# Maple5.net
KiCad netlist of a schematic drawn in EAGLE
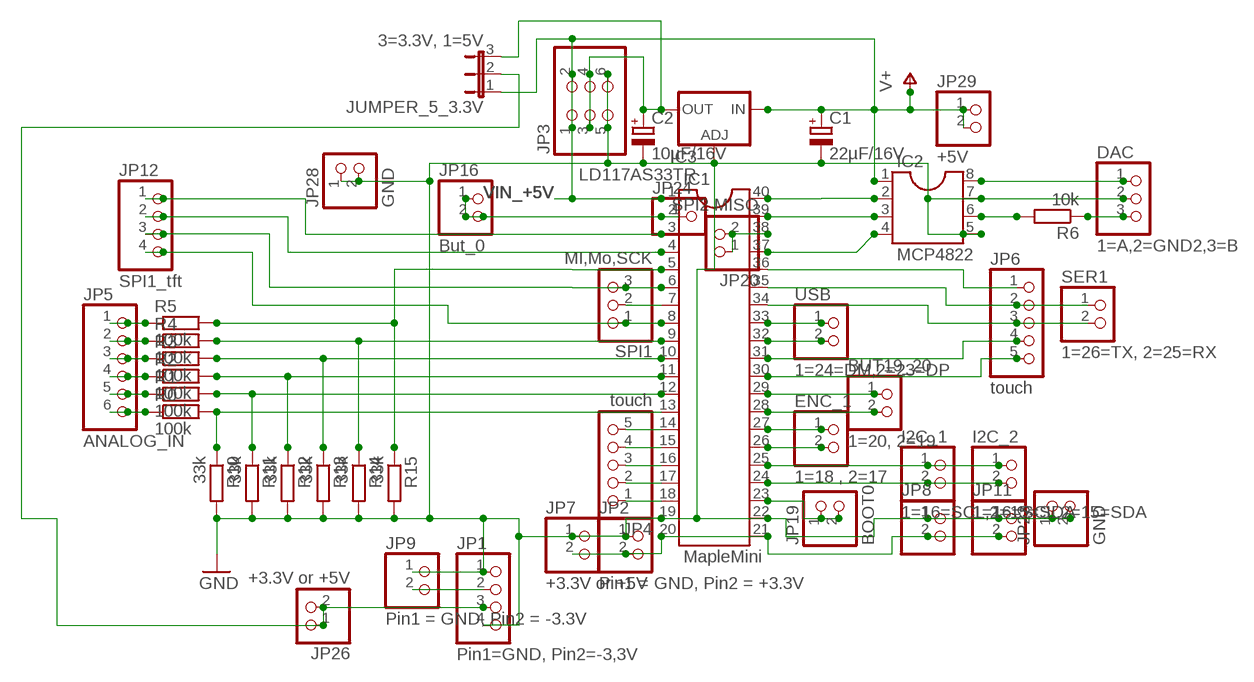
[diagram p0: schematic, sheet 1]

(export (version "E")
  (design (tool "Eeschema 10.0.6"))
  (components
    (comp (ref "BUT19_20")
      (value "1=20, 2=19")
      (footprint "eagle-import:1X02")
      (libsource (lib "eagle-import") (part "PINHD-1X2"))
    )
    (comp (ref "C1")
      (value "22µF/16V")
      (footprint "eagle-import:E5-8,5")
      (libsource (lib "eagle-import") (part "CPOL-EUE5-8.5"))
    )
    (comp (ref "C2")
      (value "10µF/16V")
      (footprint "eagle-import:E5-8,5")
      (libsource (lib "eagle-import") (part "CPOL-EUE5-8.5"))
    )
    (comp (ref "DAC")
      (value "1=A,2=GND2,3=B")
      (footprint "eagle-import:1X03")
      (libsource (lib "eagle-import") (part "PINHD-1X3"))
    )
    (comp (ref "ENC_1")
      (value "1=18 , 2=17")
      (footprint "eagle-import:1X02")
      (libsource (lib "eagle-import") (part "PINHD-1X2"))
    )
    (comp (ref "I2C_1")
      (value "1=16=SCL,2=15=SDA")
      (footprint "eagle-import:1X02")
      (libsource (lib "eagle-import") (part "PINHD-1X2"))
    )
    (comp (ref "I2C_2")
      (value "1=16=SCL,2=15=SDA")
      (footprint "eagle-import:1X02")
      (libsource (lib "eagle-import") (part "PINHD-1X2"))
    )
    (comp (ref "IC1")
      (value "MapleMini")
      (footprint "eagle-import:DIL40")
      (libsource (lib "eagle-import") (part "DIL40"))
    )
    (comp (ref "IC2")
      (value "MCP4822")
      (footprint "eagle-import:SOCKET-08")
      (libsource (lib "eagle-import") (part "DIL8S"))
    )
    (comp (ref "IC3")
      (value "LD117AS33TR")
      (footprint "eagle-import:SOT223")
      (libsource (lib "eagle-import") (part "LD117A?S33TR"))
    )
    (comp (ref "JP1")
      (value "Pin1=GND, Pin2=-3,3V")
      (footprint "eagle-import:1X04")
      (libsource (lib "eagle-import") (part "PINHD-1X4"))
    )
    (comp (ref "JP2")
      (value "Pin1 = GND, Pin2 = +3.3V")
      (footprint "eagle-import:1X02")
      (libsource (lib "eagle-import") (part "PINHD-1X2"))
    )
    (comp (ref "JP3")
      (value "PINHD-2X3")
      (footprint "eagle-import:2X03")
      (libsource (lib "eagle-import") (part "PINHD-2X3"))
    )
    (comp (ref "JP4")
      (value "touch")
      (footprint "eagle-import:1X05")
      (libsource (lib "eagle-import") (part "PINHD-1X5"))
    )
    (comp (ref "JP5")
      (value "ANALOG_IN")
      (footprint "eagle-import:1X06")
      (libsource (lib "eagle-import") (part "PINHD-1X6"))
    )
    (comp (ref "JP6")
      (value "touch")
      (footprint "eagle-import:1X05")
      (libsource (lib "eagle-import") (part "PINHD-1X5"))
    )
    (comp (ref "JP7")
      (value "+3.3V or +5V")
      (footprint "eagle-import:1X02")
      (libsource (lib "eagle-import") (part "PINHD-1X2"))
    )
    (comp (ref "JP8")
      (value "PINHD-1X2")
      (footprint "eagle-import:1X02")
      (libsource (lib "eagle-import") (part "PINHD-1X2"))
    )
    (comp (ref "JP9")
      (value "Pin1 = GND, Pin2 = -3.3V")
      (footprint "eagle-import:1X02")
      (libsource (lib "eagle-import") (part "PINHD-1X2"))
    )
    (comp (ref "JP11")
      (value "PINHD-1X2")
      (footprint "eagle-import:1X02")
      (libsource (lib "eagle-import") (part "PINHD-1X2"))
    )
    (comp (ref "JP12")
      (value "SPI1_tft")
      (footprint "eagle-import:1X04")
      (libsource (lib "eagle-import") (part "PINHD-1X4"))
    )
    (comp (ref "JP16")
      (value "But_0")
      (footprint "eagle-import:1X02")
      (libsource (lib "eagle-import") (part "PINHD-1X2"))
    )
    (comp (ref "JP19")
      (value "BOOT0")
      (footprint "eagle-import:1X02")
      (libsource (lib "eagle-import") (part "PINHD-1X2"))
    )
    (comp (ref "JP20")
      (value "SPI2 MISO")
      (footprint "eagle-import:1X02")
      (libsource (lib "eagle-import") (part "PINHD-1X2"))
    )
    (comp (ref "JP23")
      (value "GND")
      (footprint "eagle-import:1X02")
      (libsource (lib "eagle-import") (part "PINHD-1X2"))
    )
    (comp (ref "JP24")
      (value "PINHD-1X1")
      (footprint "eagle-import:1X01")
      (libsource (lib "eagle-import") (part "PINHD-1X1"))
    )
    (comp (ref "JP26")
      (value "+3.3V or +5V")
      (footprint "eagle-import:1X02")
      (libsource (lib "eagle-import") (part "PINHD-1X2"))
    )
    (comp (ref "JP28")
      (value "GND")
      (footprint "eagle-import:1X02")
      (libsource (lib "eagle-import") (part "PINHD-1X2"))
    )
    (comp (ref "JP29")
      (value "+5V")
      (footprint "eagle-import:1X02")
      (libsource (lib "eagle-import") (part "PINHD-1X2"))
    )
    (comp (ref "JUMPER_5_3.3V")
      (value "3=3.3V, 1=5V")
      (footprint "eagle-import:JP2")
      (libsource (lib "eagle-import") (part "JP2E"))
    )
    (comp (ref "R0")
      (value "100k")
      (footprint "eagle-import:0207_7")
      (libsource (lib "eagle-import") (part "R-EU_0207/7"))
    )
    (comp (ref "R1")
      (value "100k")
      (footprint "eagle-import:0207_7")
      (libsource (lib "eagle-import") (part "R-EU_0207/7"))
    )
    (comp (ref "R2")
      (value "100k")
      (footprint "eagle-import:0207_7")
      (libsource (lib "eagle-import") (part "R-EU_0207/7"))
    )
    (comp (ref "R3")
      (value "100k")
      (footprint "eagle-import:0207_7")
      (libsource (lib "eagle-import") (part "R-EU_0207/7"))
    )
    (comp (ref "R4")
      (value "100k")
      (footprint "eagle-import:0207_7")
      (libsource (lib "eagle-import") (part "R-EU_0207/7"))
    )
    (comp (ref "R5")
      (value "100k")
      (footprint "eagle-import:0207_7")
      (libsource (lib "eagle-import") (part "R-EU_0207/7"))
    )
    (comp (ref "R6")
      (value "10k")
      (footprint "eagle-import:0207_7")
      (libsource (lib "eagle-import") (part "R-EU_0207/7"))
    )
    (comp (ref "R10")
      (value "33k")
      (footprint "eagle-import:0207_7")
      (libsource (lib "eagle-import") (part "R-EU_0207/7"))
    )
    (comp (ref "R11")
      (value "33k")
      (footprint "eagle-import:0207_7")
      (libsource (lib "eagle-import") (part "R-EU_0207/7"))
    )
    (comp (ref "R12")
      (value "33k")
      (footprint "eagle-import:0207_7")
      (libsource (lib "eagle-import") (part "R-EU_0207/7"))
    )
    (comp (ref "R13")
      (value "33k")
      (footprint "eagle-import:0207_7")
      (libsource (lib "eagle-import") (part "R-EU_0207/7"))
    )
    (comp (ref "R14")
      (value "33k")
      (footprint "eagle-import:0207_7")
      (libsource (lib "eagle-import") (part "R-EU_0207/7"))
    )
    (comp (ref "R15")
      (value "33k")
      (footprint "eagle-import:0207_7")
      (libsource (lib "eagle-import") (part "R-EU_0207/7"))
    )
    (comp (ref "SER1")
      (value "1=26=TX, 2=25=RX")
      (footprint "eagle-import:1X02")
      (libsource (lib "eagle-import") (part "PINHD-1X2"))
    )
    (comp (ref "SPI1")
      (value "MI,Mo,SCK")
      (footprint "eagle-import:1X03")
      (libsource (lib "eagle-import") (part "PINHD-1X3"))
    )
    (comp (ref "USB")
      (value "1=24=DM,2=23=DP")
      (footprint "eagle-import:1X02")
      (libsource (lib "eagle-import") (part "PINHD-1X2"))
    )
  )
  (nets
    (net (code "1") (name "GND") (class "Default")
      (node (ref "C1") (pin "-") (pinfunction "-_-") (pintype "passive"))
      (node (ref "C2") (pin "-") (pinfunction "-_-") (pintype "passive"))
      (node (ref "DAC") (pin "2") (pinfunction "2_2") (pintype "passive"))
      (node (ref "IC1") (pin "19") (pinfunction "19_19") (pintype "passive"))
      (node (ref "IC1") (pin "22") (pinfunction "22_22") (pintype "passive"))
      (node (ref "IC2") (pin "5") (pinfunction "5_5") (pintype "passive"))
      (node (ref "IC2") (pin "7") (pinfunction "7_7") (pintype "passive"))
      (node (ref "IC3") (pin "1") (pinfunction "ADJ_1") (pintype "input"))
      (node (ref "JP1") (pin "1") (pinfunction "1_1") (pintype "passive"))
      (node (ref "JP1") (pin "4") (pinfunction "4_4") (pintype "passive"))
      (node (ref "JP11") (pin "1") (pinfunction "1_1") (pintype "passive"))
      (node (ref "JP2") (pin "1") (pinfunction "1_1") (pintype "passive"))
      (node (ref "JP23") (pin "1") (pinfunction "1_1") (pintype "passive"))
      (node (ref "JP23") (pin "2") (pinfunction "2_2") (pintype "passive"))
      (node (ref "JP28") (pin "1") (pinfunction "1_1") (pintype "passive"))
      (node (ref "JP28") (pin "2") (pinfunction "2_2") (pintype "passive"))
      (node (ref "JP3") (pin "5") (pinfunction "5_5") (pintype "passive"))
      (node (ref "JP3") (pin "6") (pinfunction "6_6") (pintype "passive"))
      (node (ref "JP7") (pin "1") (pinfunction "1_1") (pintype "passive"))
      (node (ref "JP8") (pin "1") (pinfunction "1_1") (pintype "passive"))
      (node (ref "JP9") (pin "1") (pinfunction "1_1") (pintype "passive"))
      (node (ref "R10") (pin "2") (pinfunction "2_2") (pintype "passive"))
      (node (ref "R11") (pin "2") (pinfunction "2_2") (pintype "passive"))
      (node (ref "R12") (pin "2") (pinfunction "2_2") (pintype "passive"))
      (node (ref "R13") (pin "2") (pinfunction "2_2") (pintype "passive"))
      (node (ref "R14") (pin "2") (pinfunction "2_2") (pintype "passive"))
      (node (ref "R15") (pin "2") (pinfunction "2_2") (pintype "passive"))
    )
    (net (code "2") (name "Net-(BUT19_20-Pad1)") (class "Default")
      (node (ref "BUT19_20") (pin "1") (pinfunction "1_1") (pintype "passive"))
      (node (ref "IC1") (pin "29") (pinfunction "29_29") (pintype "passive"))
    )
    (net (code "3") (name "Net-(BUT19_20-Pad2)") (class "Default")
      (node (ref "BUT19_20") (pin "2") (pinfunction "2_2") (pintype "passive"))
      (node (ref "IC1") (pin "28") (pinfunction "28_28") (pintype "passive"))
    )
    (net (code "4") (name "Net-(DAC-Pad1)") (class "Default")
      (node (ref "DAC") (pin "1") (pinfunction "1_1") (pintype "passive"))
      (node (ref "IC2") (pin "8") (pinfunction "8_8") (pintype "passive"))
    )
    (net (code "5") (name "Net-(DAC-Pad3)") (class "Default")
      (node (ref "DAC") (pin "3") (pinfunction "3_3") (pintype "passive"))
      (node (ref "R6") (pin "1") (pinfunction "1_1") (pintype "passive"))
    )
    (net (code "6") (name "Net-(ENC_1-Pad1)") (class "Default")
      (node (ref "ENC_1") (pin "1") (pinfunction "1_1") (pintype "passive"))
      (node (ref "IC1") (pin "27") (pinfunction "27_27") (pintype "passive"))
    )
    (net (code "7") (name "Net-(ENC_1-Pad2)") (class "Default")
      (node (ref "ENC_1") (pin "2") (pinfunction "2_2") (pintype "passive"))
      (node (ref "IC1") (pin "26") (pinfunction "26_26") (pintype "passive"))
    )
    (net (code "8") (name "Net-(I2C_1-Pad1)") (class "Default")
      (node (ref "I2C_1") (pin "1") (pinfunction "1_1") (pintype "passive"))
      (node (ref "I2C_2") (pin "1") (pinfunction "1_1") (pintype "passive"))
      (node (ref "IC1") (pin "25") (pinfunction "25_25") (pintype "passive"))
    )
    (net (code "9") (name "Net-(I2C_1-Pad2)") (class "Default")
      (node (ref "I2C_1") (pin "2") (pinfunction "2_2") (pintype "passive"))
      (node (ref "I2C_2") (pin "2") (pinfunction "2_2") (pintype "passive"))
      (node (ref "IC1") (pin "24") (pinfunction "24_24") (pintype "passive"))
    )
    (net (code "10") (name "Net-(IC1-Pad2)") (class "Default")
      (node (ref "IC1") (pin "2") (pinfunction "2_2") (pintype "passive"))
      (node (ref "JP16") (pin "1") (pinfunction "1_1") (pintype "passive"))
      (node (ref "JP16") (pin "2") (pinfunction "2_2") (pintype "passive"))
      (node (ref "JP24") (pin "1") (pinfunction "1_1") (pintype "passive"))
    )
    (net (code "11") (name "Net-(IC1-Pad3)") (class "Default")
      (node (ref "IC1") (pin "3") (pinfunction "3_3") (pintype "passive"))
      (node (ref "JP12") (pin "1") (pinfunction "1_1") (pintype "passive"))
    )
    (net (code "12") (name "Net-(IC1-Pad4)") (class "Default")
      (node (ref "IC1") (pin "4") (pinfunction "4_4") (pintype "passive"))
      (node (ref "JP12") (pin "2") (pinfunction "2_2") (pintype "passive"))
    )
    (net (code "13") (name "Net-(IC1-Pad5)") (class "Default")
      (node (ref "IC1") (pin "5") (pinfunction "5_5") (pintype "passive"))
      (node (ref "R15") (pin "1") (pinfunction "1_1") (pintype "passive"))
      (node (ref "R5") (pin "2") (pinfunction "2_2") (pintype "passive"))
    )
    (net (code "14") (name "Net-(IC1-Pad6)") (class "Default")
      (node (ref "IC1") (pin "6") (pinfunction "6_6") (pintype "passive"))
      (node (ref "JP12") (pin "3") (pinfunction "3_3") (pintype "passive"))
      (node (ref "SPI1") (pin "3") (pinfunction "3_3") (pintype "passive"))
    )
    (net (code "15") (name "Net-(IC1-Pad7)") (class "Default")
      (node (ref "IC1") (pin "7") (pinfunction "7_7") (pintype "passive"))
      (node (ref "SPI1") (pin "2") (pinfunction "2_2") (pintype "passive"))
    )
    (net (code "16") (name "Net-(IC1-Pad8)") (class "Default")
      (node (ref "IC1") (pin "8") (pinfunction "8_8") (pintype "passive"))
      (node (ref "JP12") (pin "4") (pinfunction "4_4") (pintype "passive"))
      (node (ref "SPI1") (pin "1") (pinfunction "1_1") (pintype "passive"))
    )
    (net (code "17") (name "Net-(IC1-Pad9)") (class "Default")
      (node (ref "IC1") (pin "9") (pinfunction "9_9") (pintype "passive"))
      (node (ref "R14") (pin "1") (pinfunction "1_1") (pintype "passive"))
      (node (ref "R4") (pin "2") (pinfunction "2_2") (pintype "passive"))
    )
    (net (code "18") (name "Net-(IC1-Pad10)") (class "Default")
      (node (ref "IC1") (pin "10") (pinfunction "10_10") (pintype "passive"))
      (node (ref "R13") (pin "1") (pinfunction "1_1") (pintype "passive"))
      (node (ref "R3") (pin "2") (pinfunction "2_2") (pintype "passive"))
    )
    (net (code "19") (name "Net-(IC1-Pad11)") (class "Default")
      (node (ref "IC1") (pin "11") (pinfunction "11_11") (pintype "passive"))
      (node (ref "R12") (pin "1") (pinfunction "1_1") (pintype "passive"))
      (node (ref "R2") (pin "2") (pinfunction "2_2") (pintype "passive"))
    )
    (net (code "20") (name "Net-(IC1-Pad12)") (class "Default")
      (node (ref "IC1") (pin "12") (pinfunction "12_12") (pintype "passive"))
      (node (ref "R1") (pin "2") (pinfunction "2_2") (pintype "passive"))
      (node (ref "R11") (pin "1") (pinfunction "1_1") (pintype "passive"))
    )
    (net (code "21") (name "Net-(IC1-Pad13)") (class "Default")
      (node (ref "IC1") (pin "13") (pinfunction "13_13") (pintype "passive"))
      (node (ref "R0") (pin "2") (pinfunction "2_2") (pintype "passive"))
      (node (ref "R10") (pin "1") (pinfunction "1_1") (pintype "passive"))
    )
    (net (code "22") (name "Net-(IC1-Pad14)") (class "Default")
      (node (ref "IC1") (pin "14") (pinfunction "14_14") (pintype "passive"))
      (node (ref "JP4") (pin "5") (pinfunction "5_5") (pintype "passive"))
    )
    (net (code "23") (name "Net-(IC1-Pad15)") (class "Default")
      (node (ref "IC1") (pin "15") (pinfunction "15_15") (pintype "passive"))
      (node (ref "JP4") (pin "4") (pinfunction "4_4") (pintype "passive"))
    )
    (net (code "24") (name "Net-(IC1-Pad16)") (class "Default")
      (node (ref "IC1") (pin "16") (pinfunction "16_16") (pintype "passive"))
      (node (ref "JP4") (pin "3") (pinfunction "3_3") (pintype "passive"))
    )
    (net (code "25") (name "Net-(IC1-Pad17)") (class "Default")
      (node (ref "IC1") (pin "17") (pinfunction "17_17") (pintype "passive"))
      (node (ref "JP4") (pin "2") (pinfunction "2_2") (pintype "passive"))
    )
    (net (code "26") (name "Net-(IC1-Pad18)") (class "Default")
      (node (ref "IC1") (pin "18") (pinfunction "18_18") (pintype "passive"))
      (node (ref "JP4") (pin "1") (pinfunction "1_1") (pintype "passive"))
    )
    (net (code "27") (name "Net-(IC1-Pad20)") (class "Default")
      (node (ref "IC1") (pin "20") (pinfunction "20_20") (pintype "passive"))
      (node (ref "IC1") (pin "21") (pinfunction "21_21") (pintype "passive"))
      (node (ref "JP11") (pin "2") (pinfunction "2_2") (pintype "passive"))
      (node (ref "JP2") (pin "2") (pinfunction "2_2") (pintype "passive"))
      (node (ref "JP7") (pin "2") (pinfunction "2_2") (pintype "passive"))
      (node (ref "JP8") (pin "2") (pinfunction "2_2") (pintype "passive"))
    )
    (net (code "28") (name "Net-(IC1-Pad23)") (class "Default")
      (node (ref "IC1") (pin "23") (pinfunction "23_23") (pintype "passive"))
      (node (ref "JP19") (pin "1") (pinfunction "1_1") (pintype "passive"))
      (node (ref "JP19") (pin "2") (pinfunction "2_2") (pintype "passive"))
    )
    (net (code "29") (name "Net-(IC1-Pad30)") (class "Default")
      (node (ref "IC1") (pin "30") (pinfunction "30_30") (pintype "passive"))
      (node (ref "JP6") (pin "5") (pinfunction "5_5") (pintype "passive"))
    )
    (net (code "30") (name "Net-(IC1-Pad31)") (class "Default")
      (node (ref "IC1") (pin "31") (pinfunction "31_31") (pintype "passive"))
      (node (ref "JP6") (pin "4") (pinfunction "4_4") (pintype "passive"))
    )
    (net (code "31") (name "Net-(IC1-Pad32)") (class "Default")
      (node (ref "IC1") (pin "32") (pinfunction "32_32") (pintype "passive"))
      (node (ref "USB") (pin "2") (pinfunction "2_2") (pintype "passive"))
    )
    (net (code "32") (name "Net-(IC1-Pad33)") (class "Default")
      (node (ref "IC1") (pin "33") (pinfunction "33_33") (pintype "passive"))
      (node (ref "USB") (pin "1") (pinfunction "1_1") (pintype "passive"))
    )
    (net (code "33") (name "Net-(IC1-Pad34)") (class "Default")
      (node (ref "IC1") (pin "34") (pinfunction "34_34") (pintype "passive"))
      (node (ref "JP6") (pin "3") (pinfunction "3_3") (pintype "passive"))
      (node (ref "SER1") (pin "2") (pinfunction "2_2") (pintype "passive"))
    )
    (net (code "34") (name "Net-(IC1-Pad35)") (class "Default")
      (node (ref "IC1") (pin "35") (pinfunction "35_35") (pintype "passive"))
      (node (ref "JP6") (pin "2") (pinfunction "2_2") (pintype "passive"))
      (node (ref "SER1") (pin "1") (pinfunction "1_1") (pintype "passive"))
    )
    (net (code "35") (name "Net-(IC1-Pad36)") (class "Default")
      (node (ref "IC1") (pin "36") (pinfunction "36_36") (pintype "passive"))
      (node (ref "JP6") (pin "1") (pinfunction "1_1") (pintype "passive"))
    )
    (net (code "36") (name "Net-(IC1-Pad37)") (class "Default")
      (node (ref "IC1") (pin "37") (pinfunction "37_37") (pintype "passive"))
      (node (ref "IC2") (pin "4") (pinfunction "4_4") (pintype "passive"))
    )
    (net (code "37") (name "Net-(IC1-Pad38)") (class "Default")
      (node (ref "IC1") (pin "38") (pinfunction "38_38") (pintype "passive"))
      (node (ref "JP20") (pin "1") (pinfunction "1_1") (pintype "passive"))
      (node (ref "JP20") (pin "2") (pinfunction "2_2") (pintype "passive"))
    )
    (net (code "38") (name "Net-(IC1-Pad39)") (class "Default")
      (node (ref "IC1") (pin "39") (pinfunction "39_39") (pintype "passive"))
      (node (ref "IC2") (pin "3") (pinfunction "3_3") (pintype "passive"))
    )
    (net (code "39") (name "Net-(IC1-Pad40)") (class "Default")
      (node (ref "IC1") (pin "40") (pinfunction "40_40") (pintype "passive"))
      (node (ref "IC2") (pin "2") (pinfunction "2_2") (pintype "passive"))
    )
    (net (code "40") (name "Net-(IC2-Pad6)") (class "Default")
      (node (ref "IC2") (pin "6") (pinfunction "6_6") (pintype "passive"))
      (node (ref "R6") (pin "2") (pinfunction "2_2") (pintype "passive"))
    )
    (net (code "41") (name "Net-(IC3-OUT)") (class "Default")
      (node (ref "C2") (pin "+") (pinfunction "+_+") (pintype "passive"))
      (node (ref "IC3") (pin "4") (pinfunction "OUT_4") (pintype "passive"))
      (node (ref "JP3") (pin "3") (pinfunction "3_3") (pintype "passive"))
      (node (ref "JP3") (pin "4") (pinfunction "4_4") (pintype "passive"))
      (node (ref "JUMPER_5_3.3V") (pin "3") (pinfunction "3_3") (pintype "passive"))
    )
    (net (code "42") (name "Net-(JP1-Pad2)") (class "Default")
      (node (ref "JP1") (pin "2") (pinfunction "2_2") (pintype "passive"))
      (node (ref "JP9") (pin "2") (pinfunction "2_2") (pintype "passive"))
    )
    (net (code "43") (name "Net-(JP1-Pad3)") (class "Default")
      (node (ref "JP1") (pin "3") (pinfunction "3_3") (pintype "passive"))
      (node (ref "JP26") (pin "1") (pinfunction "1_1") (pintype "passive"))
      (node (ref "JP26") (pin "2") (pinfunction "2_2") (pintype "passive"))
      (node (ref "JUMPER_5_3.3V") (pin "2") (pinfunction "2_2") (pintype "passive"))
    )
    (net (code "44") (name "Net-(JP5-Pad1)") (class "Default")
      (node (ref "JP5") (pin "1") (pinfunction "1_1") (pintype "passive"))
      (node (ref "R5") (pin "1") (pinfunction "1_1") (pintype "passive"))
    )
    (net (code "45") (name "Net-(JP5-Pad2)") (class "Default")
      (node (ref "JP5") (pin "2") (pinfunction "2_2") (pintype "passive"))
      (node (ref "R4") (pin "1") (pinfunction "1_1") (pintype "passive"))
    )
    (net (code "46") (name "Net-(JP5-Pad3)") (class "Default")
      (node (ref "JP5") (pin "3") (pinfunction "3_3") (pintype "passive"))
      (node (ref "R3") (pin "1") (pinfunction "1_1") (pintype "passive"))
    )
    (net (code "47") (name "Net-(JP5-Pad4)") (class "Default")
      (node (ref "JP5") (pin "4") (pinfunction "4_4") (pintype "passive"))
      (node (ref "R2") (pin "1") (pinfunction "1_1") (pintype "passive"))
    )
    (net (code "48") (name "Net-(JP5-Pad5)") (class "Default")
      (node (ref "JP5") (pin "5") (pinfunction "5_5") (pintype "passive"))
      (node (ref "R1") (pin "1") (pinfunction "1_1") (pintype "passive"))
    )
    (net (code "49") (name "Net-(JP5-Pad6)") (class "Default")
      (node (ref "JP5") (pin "6") (pinfunction "6_6") (pintype "passive"))
      (node (ref "R0") (pin "1") (pinfunction "1_1") (pintype "passive"))
    )
    (net (code "50") (name "V+") (class "Default")
      (node (ref "C1") (pin "+") (pinfunction "+_+") (pintype "passive"))
      (node (ref "IC1") (pin "1") (pinfunction "1_1") (pintype "passive"))
      (node (ref "IC2") (pin "1") (pinfunction "1_1") (pintype "passive"))
      (node (ref "IC3") (pin "3") (pinfunction "IN_3") (pintype "input"))
      (node (ref "JP29") (pin "1") (pinfunction "1_1") (pintype "passive"))
      (node (ref "JP29") (pin "2") (pinfunction "2_2") (pintype "passive"))
      (node (ref "JP3") (pin "1") (pinfunction "1_1") (pintype "passive"))
      (node (ref "JP3") (pin "2") (pinfunction "2_2") (pintype "passive"))
      (node (ref "JUMPER_5_3.3V") (pin "1") (pinfunction "1_1") (pintype "passive"))
    )
  )
)
